# esp-12.net
KiCad netlist of a schematic drawn in EAGLE
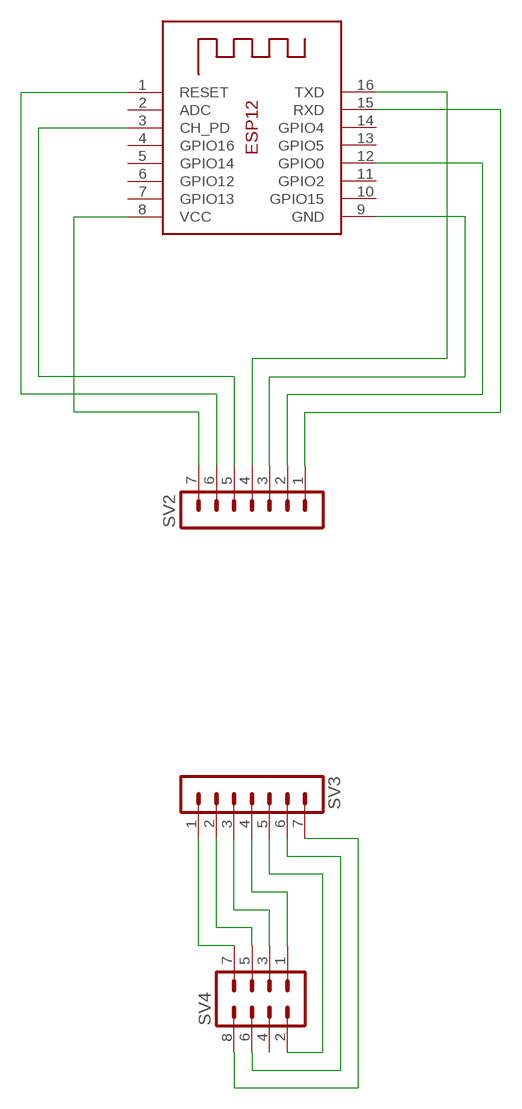
[diagram p0: schematic, sheet 1]

(export (version "E")
  (design (tool "Eeschema 10.0.6"))
  (components
    (comp (ref "SV2")
      (value "MA07-1")
      (footprint "eagle-import:MA07-1")
      (libsource (lib "eagle-import") (part "MA07-1"))
    )
    (comp (ref "SV3")
      (value "MA07-1")
      (footprint "eagle-import:MA07-1")
      (libsource (lib "eagle-import") (part "MA07-1"))
    )
    (comp (ref "SV4")
      (value "MA04-2")
      (footprint "eagle-import:MA04-2")
      (libsource (lib "eagle-import") (part "MA04-2"))
    )
    (comp (ref "X1")
      (value "ESP-12")
      (footprint "eagle-import:ESP-12")
      (libsource (lib "eagle-import") (part "ESP-12"))
    )
  )
  (nets
    (net (code "1") (name "Net-(SV3-Pad1)") (class "Default")
      (node (ref "SV3") (pin "1") (pinfunction "1_1") (pintype "passive"))
      (node (ref "SV4") (pin "7") (pinfunction "7_7") (pintype "passive"))
    )
    (net (code "2") (name "Net-(SV3-Pad2)") (class "Default")
      (node (ref "SV3") (pin "2") (pinfunction "2_2") (pintype "passive"))
      (node (ref "SV4") (pin "5") (pinfunction "5_5") (pintype "passive"))
    )
    (net (code "3") (name "Net-(SV3-Pad3)") (class "Default")
      (node (ref "SV3") (pin "3") (pinfunction "3_3") (pintype "passive"))
      (node (ref "SV4") (pin "3") (pinfunction "3_3") (pintype "passive"))
    )
    (net (code "4") (name "Net-(SV3-Pad4)") (class "Default")
      (node (ref "SV3") (pin "4") (pinfunction "4_4") (pintype "passive"))
      (node (ref "SV4") (pin "1") (pinfunction "1_1") (pintype "passive"))
    )
    (net (code "5") (name "Net-(SV3-Pad5)") (class "Default")
      (node (ref "SV3") (pin "5") (pinfunction "5_5") (pintype "passive"))
      (node (ref "SV4") (pin "2") (pinfunction "2_2") (pintype "passive"))
    )
    (net (code "6") (name "Net-(SV3-Pad6)") (class "Default")
      (node (ref "SV3") (pin "6") (pinfunction "6_6") (pintype "passive"))
      (node (ref "SV4") (pin "6") (pinfunction "6_6") (pintype "passive"))
    )
    (net (code "7") (name "Net-(SV3-Pad7)") (class "Default")
      (node (ref "SV3") (pin "7") (pinfunction "7_7") (pintype "passive"))
      (node (ref "SV4") (pin "8") (pinfunction "8_8") (pintype "passive"))
    )
    (net (code "8") (name "Net-(X1-CH_PD)") (class "Default")
      (node (ref "SV2") (pin "5") (pinfunction "5_5") (pintype "passive"))
      (node (ref "X1") (pin "3") (pinfunction "CH_PD_3") (pintype "input"))
    )
    (net (code "9") (name "Net-(X1-GND)") (class "Default")
      (node (ref "SV2") (pin "3") (pinfunction "3_3") (pintype "passive"))
      (node (ref "X1") (pin "9") (pinfunction "GND_9") (pintype "power_in"))
    )
    (net (code "10") (name "Net-(X1-GPIO0)") (class "Default")
      (node (ref "SV2") (pin "2") (pinfunction "2_2") (pintype "passive"))
      (node (ref "X1") (pin "12") (pinfunction "GPIO0_12") (pintype "bidirectional"))
    )
    (net (code "11") (name "Net-(X1-RESET)") (class "Default")
      (node (ref "SV2") (pin "6") (pinfunction "6_6") (pintype "passive"))
      (node (ref "X1") (pin "1") (pinfunction "RESET_1") (pintype "input"))
    )
    (net (code "12") (name "Net-(X1-RXD)") (class "Default")
      (node (ref "SV2") (pin "1") (pinfunction "1_1") (pintype "passive"))
      (node (ref "X1") (pin "15") (pinfunction "RXD_15") (pintype "input"))
    )
    (net (code "13") (name "Net-(X1-TXD)") (class "Default")
      (node (ref "SV2") (pin "4") (pinfunction "4_4") (pintype "passive"))
      (node (ref "X1") (pin "16") (pinfunction "TXD_16") (pintype "output"))
    )
    (net (code "14") (name "Net-(X1-VCC)") (class "Default")
      (node (ref "SV2") (pin "7") (pinfunction "7_7") (pintype "passive"))
      (node (ref "X1") (pin "8") (pinfunction "VCC_8") (pintype "power_in"))
    )
    (net (code "15") (name "unconnected-(SV4-Pad4)") (class "Default")
      (node (ref "SV4") (pin "4") (pinfunction "4_4") (pintype "passive"))
    )
    (net (code "16") (name "unconnected-(X1-ADC-Pad2)") (class "Default")
      (node (ref "X1") (pin "2") (pinfunction "ADC_2") (pintype "passive"))
    )
    (net (code "17") (name "unconnected-(X1-GPIO2-Pad11)") (class "Default")
      (node (ref "X1") (pin "11") (pinfunction "GPIO2_11") (pintype "bidirectional"))
    )
    (net (code "18") (name "unconnected-(X1-GPIO4-Pad14)") (class "Default")
      (node (ref "X1") (pin "14") (pinfunction "GPIO4_14") (pintype "bidirectional"))
    )
    (net (code "19") (name "unconnected-(X1-GPIO5-Pad13)") (class "Default")
      (node (ref "X1") (pin "13") (pinfunction "GPIO5_13") (pintype "bidirectional"))
    )
    (net (code "20") (name "unconnected-(X1-GPIO12-Pad6)") (class "Default")
      (node (ref "X1") (pin "6") (pinfunction "GPIO12_6") (pintype "bidirectional"))
    )
    (net (code "21") (name "unconnected-(X1-GPIO13-Pad7)") (class "Default")
      (node (ref "X1") (pin "7") (pinfunction "GPIO13_7") (pintype "bidirectional"))
    )
    (net (code "22") (name "unconnected-(X1-GPIO14-Pad5)") (class "Default")
      (node (ref "X1") (pin "5") (pinfunction "GPIO14_5") (pintype "bidirectional"))
    )
    (net (code "23") (name "unconnected-(X1-GPIO15-Pad10)") (class "Default")
      (node (ref "X1") (pin "10") (pinfunction "GPIO15_10") (pintype "bidirectional"))
    )
    (net (code "24") (name "unconnected-(X1-GPIO16-Pad4)") (class "Default")
      (node (ref "X1") (pin "4") (pinfunction "GPIO16_4") (pintype "bidirectional"))
    )
  )
)
